# PIC32.net
KiCad netlist of a schematic drawn in Altium Designer
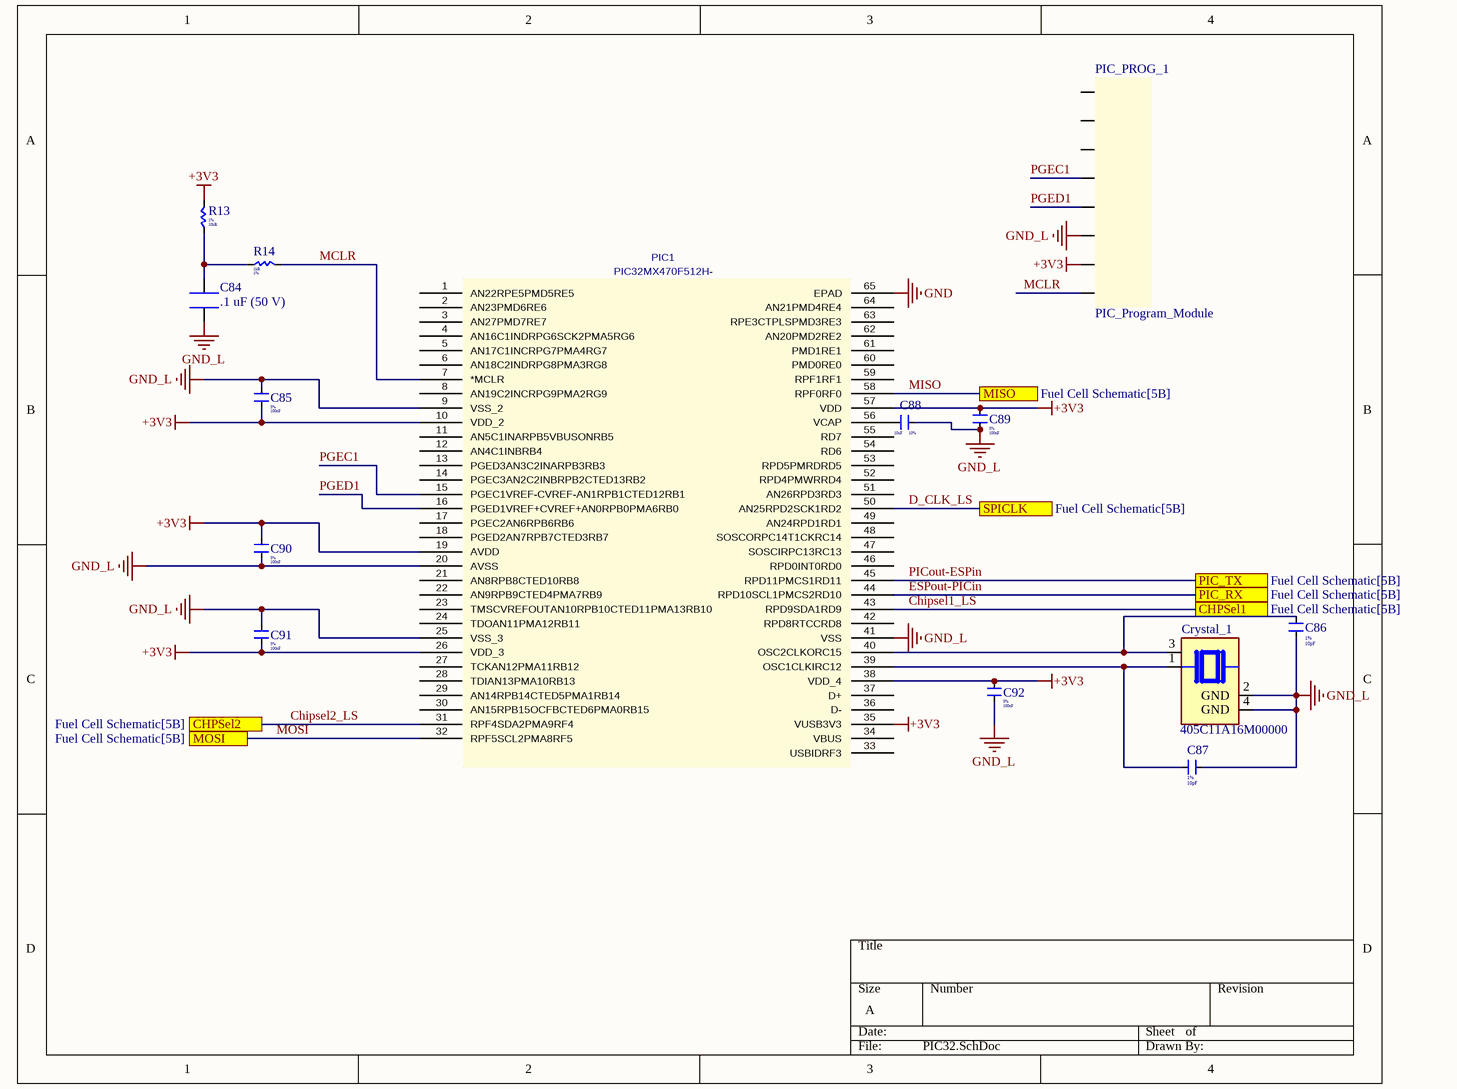
[diagram p0: PIC32.SchDoc]

(export (version "E")
  (design (tool "Eeschema 10.0.6"))
  (components
    (comp (ref "C84")
      (value ".1 uF (50 V)")
      (footprint ".1uF capacitor")
      (libsource (lib "Schlib1") (part ".1 uF cap"))
    )
    (comp (ref "C85")
      (value "~")
      (footprint "Capacitor_Kemet_0805")
      (description "Cap Ceramic 0.1uF 16V X7R 5% SMD 0805 125°C Plastic T/R")
      (fields
        (field (name "MANUFACTURER") "KEMET")
        (field (name "MANUFACTURER PART NUMBER") "C0805C104J4RACTU")
        (field (name "DISSIPATION FACTOR") "5%")
        (field (name "CAPACITANCE") "100nF")
      )
      (libsource (lib "Schlib1") (part "C0805C104J4RACTU"))
    )
    (comp (ref "C86")
      (value "~")
      (footprint "Kemet_10pF_0805")
      (description "Cap, AEC-Q200, 10PF, 50V, Mlcc, 0805;")
      (fields
        (field (name "MANUFACTURER") "KEMET")
        (field (name "MANUFACTURER PART NUMBER") "C0805C100F5GACAUTO")
        (field (name "TOLLERANCE") "1%")
        (field (name "CAPACITANCE") "10pF")
      )
      (libsource (lib "Schlib1") (part "C0805C100F5GACAUTO"))
    )
    (comp (ref "C87")
      (value "~")
      (footprint "Kemet_10pF_0805")
      (description "Cap, AEC-Q200, 10PF, 50V, Mlcc, 0805;")
      (fields
        (field (name "MANUFACTURER") "KEMET")
        (field (name "MANUFACTURER PART NUMBER") "C0805C100F5GACAUTO")
        (field (name "TOLLERANCE") "1%")
        (field (name "CAPACITANCE") "10pF")
      )
      (libsource (lib "Schlib1") (part "C0805C100F5GACAUTO"))
    )
    (comp (ref "C88")
      (value "~")
      (footprint "Capacitor_Kemet_0805")
      (description "0805 C 10uF Ceramic Multilayer Capacitor; 25 VDC; +85degC; X5R Dielec; +/-10%")
      (fields
        (field (name "MANUFACTURER") "KEMET")
        (field (name "MANUFACTURER PART NUMBER") "C0805C106K3PACTU")
        (field (name "DISSIPATION FACTOR") "10%")
        (field (name "CAPACITANCE") "10uF")
      )
      (libsource (lib "Schlib1") (part "C0805C106K3PACTU"))
    )
    (comp (ref "C89")
      (value "~")
      (footprint "Capacitor_Kemet_0805")
      (description "Cap Ceramic 0.1uF 16V X7R 5% SMD 0805 125°C Plastic T/R")
      (fields
        (field (name "MANUFACTURER") "KEMET")
        (field (name "MANUFACTURER PART NUMBER") "C0805C104J4RACTU")
        (field (name "DISSIPATION FACTOR") "5%")
        (field (name "CAPACITANCE") "100nF")
      )
      (libsource (lib "Schlib1") (part "C0805C104J4RACTU"))
    )
    (comp (ref "C90")
      (value "~")
      (footprint "Capacitor_Kemet_0805")
      (description "Cap Ceramic 0.1uF 16V X7R 5% SMD 0805 125°C Plastic T/R")
      (fields
        (field (name "MANUFACTURER") "KEMET")
        (field (name "MANUFACTURER PART NUMBER") "C0805C104J4RACTU")
        (field (name "DISSIPATION FACTOR") "5%")
        (field (name "CAPACITANCE") "100nF")
      )
      (libsource (lib "Schlib1") (part "C0805C104J4RACTU"))
    )
    (comp (ref "C91")
      (value "~")
      (footprint "Capacitor_Kemet_0805")
      (description "Cap Ceramic 0.1uF 16V X7R 5% SMD 0805 125°C Plastic T/R")
      (fields
        (field (name "MANUFACTURER") "KEMET")
        (field (name "MANUFACTURER PART NUMBER") "C0805C104J4RACTU")
        (field (name "DISSIPATION FACTOR") "5%")
        (field (name "CAPACITANCE") "100nF")
      )
      (libsource (lib "Schlib1") (part "C0805C104J4RACTU"))
    )
    (comp (ref "C92")
      (value "~")
      (footprint "Capacitor_Kemet_0805")
      (description "Cap Ceramic 0.1uF 16V X7R 5% SMD 0805 125°C Plastic T/R")
      (fields
        (field (name "MANUFACTURER") "KEMET")
        (field (name "MANUFACTURER PART NUMBER") "C0805C104J4RACTU")
        (field (name "DISSIPATION FACTOR") "5%")
        (field (name "CAPACITANCE") "100nF")
      )
      (libsource (lib "Schlib1") (part "C0805C104J4RACTU"))
    )
    (comp (ref "Crystal_1")
      (value "405C11A16M00000")
      (footprint "XTAL_405C11A16M00000")
      (description "CRYSTAL 16.0000MHZ 10PF SMD")
      (fields
        (field (name "DIGI-KEY_PART_NUMBER") "CTX834TR-ND")
        (field (name "MF") "CTS-Frequency Controls")
      )
      (libsource (lib "Schlib1") (part "405C11A16M00000"))
    )
    (comp (ref "PIC1")
      (value "PIC32MX470F512H-")
      (footprint "Quad64_2")
      (fields
        (field (name "MANUFACTURER_PART_NUMBER") "PIC32MX470F512H-I/MR")
        (field (name "COPYRIGHT") "Copyright (C) 2023 Ultra Librarian. All rights reserved.")
      )
      (libsource (lib "Schlib1") (part "PIC32MX470F512H-"))
    )
    (comp (ref "PIC_PROG_1")
      (value "PIC_Program_Module")
      (footprint "PIC_32_POD")
      (libsource (lib "Schlib1") (part "PIC_Program_Module"))
    )
    (comp (ref "R13")
      (value "~")
      (footprint "Resistor_YAGEO_0805")
      (description "RES 10K OHM 1% 1/8W 0805")
      (fields
        (field (name "MANUFACTURER") "Yageo")
        (field (name "MANUFACTURER PART NUMBER") "RC0805FR-1010KL")
        (field (name "TOLERANCE") "1%")
        (field (name "RESISTANCE") "10kR")
      )
      (libsource (lib "Schlib1") (part "RC0805FR-1010KL"))
    )
    (comp (ref "R14")
      (value "~")
      (footprint "Resistor_YAGEO_0805")
      (description "Res Thick Film 0805 1K Ohm 1% 0.125W(1/8W) ±100ppm/C Pad SMD T/R")
      (fields
        (field (name "MANUFACTURER") "Yageo")
        (field (name "MANUFACTURER PART NUMBER") "RC0805FR-071KP")
        (field (name "RESISTANCE") "1kR")
        (field (name "TOLERANCE") "1%")
      )
      (libsource (lib "Schlib1") (part "RC0805FR-071KP"))
    )
  )
  (nets
    (net (code "1") (name "+3V3") (class "Default")
      (node (ref "C85") (pin "1") (pinfunction "1_1") (pintype "passive"))
      (node (ref "C89") (pin "2") (pinfunction "2_2") (pintype "passive"))
      (node (ref "C90") (pin "2") (pinfunction "2_2") (pintype "passive"))
      (node (ref "C91") (pin "1") (pinfunction "1_1") (pintype "passive"))
      (node (ref "C92") (pin "2") (pinfunction "2_2") (pintype "passive"))
      (node (ref "PIC1") (pin "10") (pinfunction "VDD_2_10") (pintype "passive"))
      (node (ref "PIC1") (pin "19") (pinfunction "AVDD_19") (pintype "passive"))
      (node (ref "PIC1") (pin "26") (pinfunction "VDD_3_26") (pintype "passive"))
      (node (ref "PIC1") (pin "35") (pinfunction "VUSB3V3_35") (pintype "passive"))
      (node (ref "PIC1") (pin "38") (pinfunction "VDD_4_38") (pintype "passive"))
      (node (ref "PIC1") (pin "57") (pinfunction "VDD_57") (pintype "passive"))
      (node (ref "PIC_PROG_1") (pin "2") (pinfunction "VDD_2") (pintype "passive"))
      (node (ref "R13") (pin "2") (pinfunction "2_2") (pintype "passive"))
    )
    (net (code "2") (name "/Chipsel1_LS") (class "Default")
      (node (ref "PIC1") (pin "43") (pinfunction "RPD9SDA1RD9_43") (pintype "passive"))
    )
    (net (code "3") (name "/Chipsel2_LS") (class "Default")
      (node (ref "PIC1") (pin "31") (pinfunction "RPF4SDA2PMA9RF4_31") (pintype "passive"))
    )
    (net (code "4") (name "/D_CLK_LS") (class "Default")
      (node (ref "PIC1") (pin "50") (pinfunction "AN25RPD2SCK1RD2_50") (pintype "passive"))
    )
    (net (code "5") (name "/ESPout-PICin") (class "Default")
      (node (ref "PIC1") (pin "44") (pinfunction "RPD10SCL1PMCS2RD10_44") (pintype "passive"))
    )
    (net (code "6") (name "/MCLR") (class "Default")
      (node (ref "PIC1") (pin "7") (pinfunction "*MCLR_7") (pintype "passive"))
      (node (ref "PIC_PROG_1") (pin "1") (pinfunction "MCLR_1") (pintype "passive"))
      (node (ref "R14") (pin "2") (pinfunction "2_2") (pintype "passive"))
    )
    (net (code "7") (name "/MISO") (class "Default")
      (node (ref "PIC1") (pin "58") (pinfunction "RPF0RF0_58") (pintype "passive"))
    )
    (net (code "8") (name "/MOSI") (class "Default")
      (node (ref "PIC1") (pin "32") (pinfunction "RPF5SCL2PMA8RF5_32") (pintype "passive"))
    )
    (net (code "9") (name "/PGEC1") (class "Default")
      (node (ref "PIC1") (pin "15") (pinfunction "PGEC1VREF-CVREF-AN1RPB1CTED12RB1_15") (pintype "passive"))
      (node (ref "PIC_PROG_1") (pin "5") (pinfunction "PGEC_5") (pintype "passive"))
    )
    (net (code "10") (name "/PGED1") (class "Default")
      (node (ref "PIC1") (pin "16") (pinfunction "PGED1VREF+CVREF+AN0RPB0PMA6RB0_16") (pintype "passive"))
      (node (ref "PIC_PROG_1") (pin "4") (pinfunction "PGED_4") (pintype "passive"))
    )
    (net (code "11") (name "/PICout-ESPin") (class "Default")
      (node (ref "PIC1") (pin "45") (pinfunction "RPD11PMCS1RD11_45") (pintype "passive"))
    )
    (net (code "12") (name "GND") (class "Default")
      (node (ref "PIC1") (pin "65") (pinfunction "EPAD_65") (pintype "passive"))
    )
    (net (code "13") (name "GND_L") (class "Default")
      (node (ref "C84") (pin "2") (pinfunction "2_2") (pintype "passive"))
      (node (ref "C85") (pin "2") (pinfunction "2_2") (pintype "passive"))
      (node (ref "C86") (pin "2") (pinfunction "2_2") (pintype "passive"))
      (node (ref "C87") (pin "1") (pinfunction "1_1") (pintype "passive"))
      (node (ref "C88") (pin "2") (pinfunction "2_2") (pintype "passive"))
      (node (ref "C89") (pin "1") (pinfunction "1_1") (pintype "passive"))
      (node (ref "C90") (pin "1") (pinfunction "1_1") (pintype "passive"))
      (node (ref "C91") (pin "2") (pinfunction "2_2") (pintype "passive"))
      (node (ref "C92") (pin "1") (pinfunction "1_1") (pintype "passive"))
      (node (ref "Crystal_1") (pin "2") (pinfunction "GND_2") (pintype "power_in"))
      (node (ref "Crystal_1") (pin "4") (pinfunction "GND_4") (pintype "power_in"))
      (node (ref "PIC1") (pin "20") (pinfunction "AVSS_20") (pintype "passive"))
      (node (ref "PIC1") (pin "25") (pinfunction "VSS_3_25") (pintype "passive"))
      (node (ref "PIC1") (pin "41") (pinfunction "VSS_41") (pintype "passive"))
      (node (ref "PIC1") (pin "9") (pinfunction "VSS_2_9") (pintype "passive"))
      (node (ref "PIC_PROG_1") (pin "3") (pinfunction "GND_3") (pintype "passive"))
    )
    (net (code "14") (name "Net-(C84-Pad1)") (class "Default")
      (node (ref "C84") (pin "1") (pinfunction "1_1") (pintype "passive"))
      (node (ref "R13") (pin "1") (pinfunction "1_1") (pintype "passive"))
      (node (ref "R14") (pin "1") (pinfunction "1_1") (pintype "passive"))
    )
    (net (code "15") (name "Net-(Crystal_1-2)") (class "Default")
      (node (ref "C86") (pin "1") (pinfunction "1_1") (pintype "passive"))
      (node (ref "Crystal_1") (pin "3") (pinfunction "2_3") (pintype "passive"))
      (node (ref "PIC1") (pin "40") (pinfunction "OSC2CLKORC15_40") (pintype "passive"))
    )
    (net (code "16") (name "Net-(PIC1-OSC1CLKIRC12)") (class "Default")
      (node (ref "C87") (pin "2") (pinfunction "2_2") (pintype "passive"))
      (node (ref "Crystal_1") (pin "1") (pinfunction "1_1") (pintype "passive"))
      (node (ref "PIC1") (pin "39") (pinfunction "OSC1CLKIRC12_39") (pintype "passive"))
    )
    (net (code "17") (name "Net-(PIC1-VCAP)") (class "Default")
      (node (ref "C88") (pin "1") (pinfunction "1_1") (pintype "passive"))
      (node (ref "PIC1") (pin "56") (pinfunction "VCAP_56") (pintype "passive"))
    )
    (net (code "18") (name "unconnected-(PIC1-AN4C1INBRB4-Pad12)") (class "Default")
      (node (ref "PIC1") (pin "12") (pinfunction "AN4C1INBRB4_12") (pintype "passive"))
    )
    (net (code "19") (name "unconnected-(PIC1-AN5C1INARPB5VBUSONRB5-Pad11)") (class "Default")
      (node (ref "PIC1") (pin "11") (pinfunction "AN5C1INARPB5VBUSONRB5_11") (pintype "passive"))
    )
    (net (code "20") (name "unconnected-(PIC1-AN8RPB8CTED10RB8-Pad21)") (class "Default")
      (node (ref "PIC1") (pin "21") (pinfunction "AN8RPB8CTED10RB8_21") (pintype "passive"))
    )
    (net (code "21") (name "unconnected-(PIC1-AN9RPB9CTED4PMA7RB9-Pad22)") (class "Default")
      (node (ref "PIC1") (pin "22") (pinfunction "AN9RPB9CTED4PMA7RB9_22") (pintype "passive"))
    )
    (net (code "22") (name "unconnected-(PIC1-AN14RPB14CTED5PMA1RB14-Pad29)") (class "Default")
      (node (ref "PIC1") (pin "29") (pinfunction "AN14RPB14CTED5PMA1RB14_29") (pintype "passive"))
    )
    (net (code "23") (name "unconnected-(PIC1-AN15RPB15OCFBCTED6PMA0RB15-Pad30)") (class "Default")
      (node (ref "PIC1") (pin "30") (pinfunction "AN15RPB15OCFBCTED6PMA0RB15_30") (pintype "passive"))
    )
    (net (code "24") (name "unconnected-(PIC1-AN16C1INDRPG6SCK2PMA5RG6-Pad4)") (class "Default")
      (node (ref "PIC1") (pin "4") (pinfunction "AN16C1INDRPG6SCK2PMA5RG6_4") (pintype "passive"))
    )
    (net (code "25") (name "unconnected-(PIC1-AN17C1INCRPG7PMA4RG7-Pad5)") (class "Default")
      (node (ref "PIC1") (pin "5") (pinfunction "AN17C1INCRPG7PMA4RG7_5") (pintype "passive"))
    )
    (net (code "26") (name "unconnected-(PIC1-AN18C2INDRPG8PMA3RG8-Pad6)") (class "Default")
      (node (ref "PIC1") (pin "6") (pinfunction "AN18C2INDRPG8PMA3RG8_6") (pintype "passive"))
    )
    (net (code "27") (name "unconnected-(PIC1-AN19C2INCRPG9PMA2RG9-Pad8)") (class "Default")
      (node (ref "PIC1") (pin "8") (pinfunction "AN19C2INCRPG9PMA2RG9_8") (pintype "passive"))
    )
    (net (code "28") (name "unconnected-(PIC1-AN20PMD2RE2-Pad62)") (class "Default")
      (node (ref "PIC1") (pin "62") (pinfunction "AN20PMD2RE2_62") (pintype "passive"))
    )
    (net (code "29") (name "unconnected-(PIC1-AN21PMD4RE4-Pad64)") (class "Default")
      (node (ref "PIC1") (pin "64") (pinfunction "AN21PMD4RE4_64") (pintype "passive"))
    )
    (net (code "30") (name "unconnected-(PIC1-AN22RPE5PMD5RE5-Pad1)") (class "Default")
      (node (ref "PIC1") (pin "1") (pinfunction "AN22RPE5PMD5RE5_1") (pintype "passive"))
    )
    (net (code "31") (name "unconnected-(PIC1-AN23PMD6RE6-Pad2)") (class "Default")
      (node (ref "PIC1") (pin "2") (pinfunction "AN23PMD6RE6_2") (pintype "passive"))
    )
    (net (code "32") (name "unconnected-(PIC1-AN24RPD1RD1-Pad49)") (class "Default")
      (node (ref "PIC1") (pin "49") (pinfunction "AN24RPD1RD1_49") (pintype "passive"))
    )
    (net (code "33") (name "unconnected-(PIC1-AN26RPD3RD3-Pad51)") (class "Default")
      (node (ref "PIC1") (pin "51") (pinfunction "AN26RPD3RD3_51") (pintype "passive"))
    )
    (net (code "34") (name "unconnected-(PIC1-AN27PMD7RE7-Pad3)") (class "Default")
      (node (ref "PIC1") (pin "3") (pinfunction "AN27PMD7RE7_3") (pintype "passive"))
    )
    (net (code "35") (name "unconnected-(PIC1-D+-Pad37)") (class "Default")
      (node (ref "PIC1") (pin "37") (pinfunction "D+_37") (pintype "passive"))
    )
    (net (code "36") (name "unconnected-(PIC1-D--Pad36)") (class "Default")
      (node (ref "PIC1") (pin "36") (pinfunction "D-_36") (pintype "passive"))
    )
    (net (code "37") (name "unconnected-(PIC1-PGEC2AN6RPB6RB6-Pad17)") (class "Default")
      (node (ref "PIC1") (pin "17") (pinfunction "PGEC2AN6RPB6RB6_17") (pintype "passive"))
    )
    (net (code "38") (name "unconnected-(PIC1-PGEC3AN2C2INBRPB2CTED13RB2-Pad14)") (class "Default")
      (node (ref "PIC1") (pin "14") (pinfunction "PGEC3AN2C2INBRPB2CTED13RB2_14") (pintype "passive"))
    )
    (net (code "39") (name "unconnected-(PIC1-PGED2AN7RPB7CTED3RB7-Pad18)") (class "Default")
      (node (ref "PIC1") (pin "18") (pinfunction "PGED2AN7RPB7CTED3RB7_18") (pintype "passive"))
    )
    (net (code "40") (name "unconnected-(PIC1-PGED3AN3C2INARPB3RB3-Pad13)") (class "Default")
      (node (ref "PIC1") (pin "13") (pinfunction "PGED3AN3C2INARPB3RB3_13") (pintype "passive"))
    )
    (net (code "41") (name "unconnected-(PIC1-PMD0RE0-Pad60)") (class "Default")
      (node (ref "PIC1") (pin "60") (pinfunction "PMD0RE0_60") (pintype "passive"))
    )
    (net (code "42") (name "unconnected-(PIC1-PMD1RE1-Pad61)") (class "Default")
      (node (ref "PIC1") (pin "61") (pinfunction "PMD1RE1_61") (pintype "passive"))
    )
    (net (code "43") (name "unconnected-(PIC1-RD6-Pad54)") (class "Default")
      (node (ref "PIC1") (pin "54") (pinfunction "RD6_54") (pintype "passive"))
    )
    (net (code "44") (name "unconnected-(PIC1-RD7-Pad55)") (class "Default")
      (node (ref "PIC1") (pin "55") (pinfunction "RD7_55") (pintype "passive"))
    )
    (net (code "45") (name "unconnected-(PIC1-RPD0INT0RD0-Pad46)") (class "Default")
      (node (ref "PIC1") (pin "46") (pinfunction "RPD0INT0RD0_46") (pintype "passive"))
    )
    (net (code "46") (name "unconnected-(PIC1-RPD4PMWRRD4-Pad52)") (class "Default")
      (node (ref "PIC1") (pin "52") (pinfunction "RPD4PMWRRD4_52") (pintype "passive"))
    )
    (net (code "47") (name "unconnected-(PIC1-RPD5PMRDRD5-Pad53)") (class "Default")
      (node (ref "PIC1") (pin "53") (pinfunction "RPD5PMRDRD5_53") (pintype "passive"))
    )
    (net (code "48") (name "unconnected-(PIC1-RPD8RTCCRD8-Pad42)") (class "Default")
      (node (ref "PIC1") (pin "42") (pinfunction "RPD8RTCCRD8_42") (pintype "passive"))
    )
    (net (code "49") (name "unconnected-(PIC1-RPE3CTPLSPMD3RE3-Pad63)") (class "Default")
      (node (ref "PIC1") (pin "63") (pinfunction "RPE3CTPLSPMD3RE3_63") (pintype "passive"))
    )
    (net (code "50") (name "unconnected-(PIC1-RPF1RF1-Pad59)") (class "Default")
      (node (ref "PIC1") (pin "59") (pinfunction "RPF1RF1_59") (pintype "passive"))
    )
    (net (code "51") (name "unconnected-(PIC1-SOSCIRPC13RC13-Pad47)") (class "Default")
      (node (ref "PIC1") (pin "47") (pinfunction "SOSCIRPC13RC13_47") (pintype "passive"))
    )
    (net (code "52") (name "unconnected-(PIC1-SOSCORPC14T1CKRC14-Pad48)") (class "Default")
      (node (ref "PIC1") (pin "48") (pinfunction "SOSCORPC14T1CKRC14_48") (pintype "passive"))
    )
    (net (code "53") (name "unconnected-(PIC1-TCKAN12PMA11RB12-Pad27)") (class "Default")
      (node (ref "PIC1") (pin "27") (pinfunction "TCKAN12PMA11RB12_27") (pintype "passive"))
    )
    (net (code "54") (name "unconnected-(PIC1-TDIAN13PMA10RB13-Pad28)") (class "Default")
      (node (ref "PIC1") (pin "28") (pinfunction "TDIAN13PMA10RB13_28") (pintype "passive"))
    )
    (net (code "55") (name "unconnected-(PIC1-TDOAN11PMA12RB11-Pad24)") (class "Default")
      (node (ref "PIC1") (pin "24") (pinfunction "TDOAN11PMA12RB11_24") (pintype "passive"))
    )
    (net (code "56") (name "unconnected-(PIC1-TMSCVREFOUTAN10RPB10CTED11PMA13RB10-Pad23)") (class "Default")
      (node (ref "PIC1") (pin "23") (pinfunction "TMSCVREFOUTAN10RPB10CTED11PMA13RB10_23") (pintype "passive"))
    )
    (net (code "57") (name "unconnected-(PIC1-USBIDRF3-Pad33)") (class "Default")
      (node (ref "PIC1") (pin "33") (pinfunction "USBIDRF3_33") (pintype "passive"))
    )
    (net (code "58") (name "unconnected-(PIC1-VBUS-Pad34)") (class "Default")
      (node (ref "PIC1") (pin "34") (pinfunction "VBUS_34") (pintype "passive"))
    )
    (net (code "59") (name "unconnected-(PIC_PROG_1-Pad6)") (class "Default")
      (node (ref "PIC_PROG_1") (pin "6") (pinfunction "6_6") (pintype "passive"))
    )
    (net (code "60") (name "unconnected-(PIC_PROG_1-Pad7)") (class "Default")
      (node (ref "PIC_PROG_1") (pin "7") (pinfunction "7_7") (pintype "passive"))
    )
    (net (code "61") (name "unconnected-(PIC_PROG_1-Pad8)") (class "Default")
      (node (ref "PIC_PROG_1") (pin "8") (pinfunction "8_8") (pintype "passive"))
    )
  )
)
